# SubBus10.net
KiCad netlist of a schematic drawn in Altium Designer
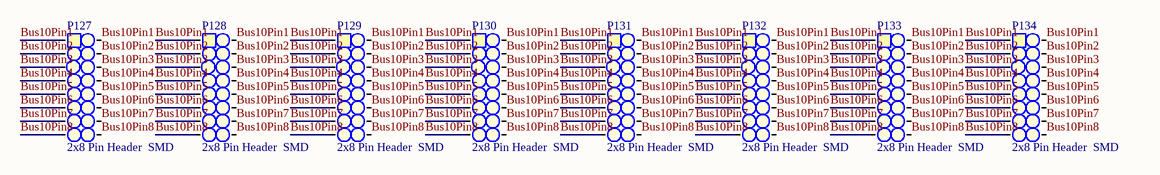
[diagram p0: SubBus10.SchDoc]

(export (version "E")
  (design (tool "Eeschema 10.0.6"))
  (components
    (comp (ref "P127")
      (value "2x8 Pin Header  SMD")
      (footprint "2X8_SMD_PH_2.54")
      (description "2.54mm, SMD")
      (libsource (lib "jclib") (part "2x8 Pin Header  SMD"))
    )
    (comp (ref "P128")
      (value "2x8 Pin Header  SMD")
      (footprint "2X8_SMD_PH_2.54")
      (description "2.54mm, SMD")
      (libsource (lib "jclib") (part "2x8 Pin Header  SMD"))
    )
    (comp (ref "P129")
      (value "2x8 Pin Header  SMD")
      (footprint "2X8_SMD_PH_2.54")
      (description "2.54mm, SMD")
      (libsource (lib "jclib") (part "2x8 Pin Header  SMD"))
    )
    (comp (ref "P130")
      (value "2x8 Pin Header  SMD")
      (footprint "2X8_SMD_PH_2.54")
      (description "2.54mm, SMD")
      (libsource (lib "jclib") (part "2x8 Pin Header  SMD"))
    )
    (comp (ref "P131")
      (value "2x8 Pin Header  SMD")
      (footprint "2X8_SMD_PH_2.54")
      (description "2.54mm, SMD")
      (libsource (lib "jclib") (part "2x8 Pin Header  SMD"))
    )
    (comp (ref "P132")
      (value "2x8 Pin Header  SMD")
      (footprint "2X8_SMD_PH_2.54")
      (description "2.54mm, SMD")
      (libsource (lib "jclib") (part "2x8 Pin Header  SMD"))
    )
    (comp (ref "P133")
      (value "2x8 Pin Header  SMD")
      (footprint "2X8_SMD_PH_2.54")
      (description "2.54mm, SMD")
      (libsource (lib "jclib") (part "2x8 Pin Header  SMD"))
    )
    (comp (ref "P134")
      (value "2x8 Pin Header  SMD")
      (footprint "2X8_SMD_PH_2.54")
      (description "2.54mm, SMD")
      (libsource (lib "jclib") (part "2x8 Pin Header  SMD"))
    )
  )
  (nets
    (net (code "1") (name "/Bus10Pin1") (class "Default")
      (node (ref "P127") (pin "1") (pinfunction "1_1") (pintype "passive"))
      (node (ref "P127") (pin "16") (pinfunction "16_16") (pintype "passive"))
      (node (ref "P128") (pin "1") (pinfunction "1_1") (pintype "passive"))
      (node (ref "P128") (pin "16") (pinfunction "16_16") (pintype "passive"))
      (node (ref "P129") (pin "1") (pinfunction "1_1") (pintype "passive"))
      (node (ref "P129") (pin "16") (pinfunction "16_16") (pintype "passive"))
      (node (ref "P130") (pin "1") (pinfunction "1_1") (pintype "passive"))
      (node (ref "P130") (pin "16") (pinfunction "16_16") (pintype "passive"))
      (node (ref "P131") (pin "1") (pinfunction "1_1") (pintype "passive"))
      (node (ref "P131") (pin "16") (pinfunction "16_16") (pintype "passive"))
      (node (ref "P132") (pin "1") (pinfunction "1_1") (pintype "passive"))
      (node (ref "P132") (pin "16") (pinfunction "16_16") (pintype "passive"))
      (node (ref "P133") (pin "1") (pinfunction "1_1") (pintype "passive"))
      (node (ref "P133") (pin "16") (pinfunction "16_16") (pintype "passive"))
      (node (ref "P134") (pin "1") (pinfunction "1_1") (pintype "passive"))
      (node (ref "P134") (pin "16") (pinfunction "16_16") (pintype "passive"))
    )
    (net (code "2") (name "/Bus10Pin2") (class "Default")
      (node (ref "P127") (pin "15") (pinfunction "15_15") (pintype "passive"))
      (node (ref "P127") (pin "2") (pinfunction "2_2") (pintype "passive"))
      (node (ref "P128") (pin "15") (pinfunction "15_15") (pintype "passive"))
      (node (ref "P128") (pin "2") (pinfunction "2_2") (pintype "passive"))
      (node (ref "P129") (pin "15") (pinfunction "15_15") (pintype "passive"))
      (node (ref "P129") (pin "2") (pinfunction "2_2") (pintype "passive"))
      (node (ref "P130") (pin "15") (pinfunction "15_15") (pintype "passive"))
      (node (ref "P130") (pin "2") (pinfunction "2_2") (pintype "passive"))
      (node (ref "P131") (pin "15") (pinfunction "15_15") (pintype "passive"))
      (node (ref "P131") (pin "2") (pinfunction "2_2") (pintype "passive"))
      (node (ref "P132") (pin "15") (pinfunction "15_15") (pintype "passive"))
      (node (ref "P132") (pin "2") (pinfunction "2_2") (pintype "passive"))
      (node (ref "P133") (pin "15") (pinfunction "15_15") (pintype "passive"))
      (node (ref "P133") (pin "2") (pinfunction "2_2") (pintype "passive"))
      (node (ref "P134") (pin "15") (pinfunction "15_15") (pintype "passive"))
      (node (ref "P134") (pin "2") (pinfunction "2_2") (pintype "passive"))
    )
    (net (code "3") (name "/Bus10Pin3") (class "Default")
      (node (ref "P127") (pin "14") (pinfunction "14_14") (pintype "passive"))
      (node (ref "P127") (pin "3") (pinfunction "3_3") (pintype "passive"))
      (node (ref "P128") (pin "14") (pinfunction "14_14") (pintype "passive"))
      (node (ref "P128") (pin "3") (pinfunction "3_3") (pintype "passive"))
      (node (ref "P129") (pin "14") (pinfunction "14_14") (pintype "passive"))
      (node (ref "P129") (pin "3") (pinfunction "3_3") (pintype "passive"))
      (node (ref "P130") (pin "14") (pinfunction "14_14") (pintype "passive"))
      (node (ref "P130") (pin "3") (pinfunction "3_3") (pintype "passive"))
      (node (ref "P131") (pin "14") (pinfunction "14_14") (pintype "passive"))
      (node (ref "P131") (pin "3") (pinfunction "3_3") (pintype "passive"))
      (node (ref "P132") (pin "14") (pinfunction "14_14") (pintype "passive"))
      (node (ref "P132") (pin "3") (pinfunction "3_3") (pintype "passive"))
      (node (ref "P133") (pin "14") (pinfunction "14_14") (pintype "passive"))
      (node (ref "P133") (pin "3") (pinfunction "3_3") (pintype "passive"))
      (node (ref "P134") (pin "14") (pinfunction "14_14") (pintype "passive"))
      (node (ref "P134") (pin "3") (pinfunction "3_3") (pintype "passive"))
    )
    (net (code "4") (name "/Bus10Pin4") (class "Default")
      (node (ref "P127") (pin "13") (pinfunction "13_13") (pintype "passive"))
      (node (ref "P127") (pin "4") (pinfunction "4_4") (pintype "passive"))
      (node (ref "P128") (pin "13") (pinfunction "13_13") (pintype "passive"))
      (node (ref "P128") (pin "4") (pinfunction "4_4") (pintype "passive"))
      (node (ref "P129") (pin "13") (pinfunction "13_13") (pintype "passive"))
      (node (ref "P129") (pin "4") (pinfunction "4_4") (pintype "passive"))
      (node (ref "P130") (pin "13") (pinfunction "13_13") (pintype "passive"))
      (node (ref "P130") (pin "4") (pinfunction "4_4") (pintype "passive"))
      (node (ref "P131") (pin "13") (pinfunction "13_13") (pintype "passive"))
      (node (ref "P131") (pin "4") (pinfunction "4_4") (pintype "passive"))
      (node (ref "P132") (pin "13") (pinfunction "13_13") (pintype "passive"))
      (node (ref "P132") (pin "4") (pinfunction "4_4") (pintype "passive"))
      (node (ref "P133") (pin "13") (pinfunction "13_13") (pintype "passive"))
      (node (ref "P133") (pin "4") (pinfunction "4_4") (pintype "passive"))
      (node (ref "P134") (pin "13") (pinfunction "13_13") (pintype "passive"))
      (node (ref "P134") (pin "4") (pinfunction "4_4") (pintype "passive"))
    )
    (net (code "5") (name "/Bus10Pin5") (class "Default")
      (node (ref "P127") (pin "12") (pinfunction "12_12") (pintype "passive"))
      (node (ref "P127") (pin "5") (pinfunction "5_5") (pintype "passive"))
      (node (ref "P128") (pin "12") (pinfunction "12_12") (pintype "passive"))
      (node (ref "P128") (pin "5") (pinfunction "5_5") (pintype "passive"))
      (node (ref "P129") (pin "12") (pinfunction "12_12") (pintype "passive"))
      (node (ref "P129") (pin "5") (pinfunction "5_5") (pintype "passive"))
      (node (ref "P130") (pin "12") (pinfunction "12_12") (pintype "passive"))
      (node (ref "P130") (pin "5") (pinfunction "5_5") (pintype "passive"))
      (node (ref "P131") (pin "12") (pinfunction "12_12") (pintype "passive"))
      (node (ref "P131") (pin "5") (pinfunction "5_5") (pintype "passive"))
      (node (ref "P132") (pin "12") (pinfunction "12_12") (pintype "passive"))
      (node (ref "P132") (pin "5") (pinfunction "5_5") (pintype "passive"))
      (node (ref "P133") (pin "12") (pinfunction "12_12") (pintype "passive"))
      (node (ref "P133") (pin "5") (pinfunction "5_5") (pintype "passive"))
      (node (ref "P134") (pin "12") (pinfunction "12_12") (pintype "passive"))
      (node (ref "P134") (pin "5") (pinfunction "5_5") (pintype "passive"))
    )
    (net (code "6") (name "/Bus10Pin6") (class "Default")
      (node (ref "P127") (pin "11") (pinfunction "11_11") (pintype "passive"))
      (node (ref "P127") (pin "6") (pinfunction "6_6") (pintype "passive"))
      (node (ref "P128") (pin "11") (pinfunction "11_11") (pintype "passive"))
      (node (ref "P128") (pin "6") (pinfunction "6_6") (pintype "passive"))
      (node (ref "P129") (pin "11") (pinfunction "11_11") (pintype "passive"))
      (node (ref "P129") (pin "6") (pinfunction "6_6") (pintype "passive"))
      (node (ref "P130") (pin "11") (pinfunction "11_11") (pintype "passive"))
      (node (ref "P130") (pin "6") (pinfunction "6_6") (pintype "passive"))
      (node (ref "P131") (pin "11") (pinfunction "11_11") (pintype "passive"))
      (node (ref "P131") (pin "6") (pinfunction "6_6") (pintype "passive"))
      (node (ref "P132") (pin "11") (pinfunction "11_11") (pintype "passive"))
      (node (ref "P132") (pin "6") (pinfunction "6_6") (pintype "passive"))
      (node (ref "P133") (pin "11") (pinfunction "11_11") (pintype "passive"))
      (node (ref "P133") (pin "6") (pinfunction "6_6") (pintype "passive"))
      (node (ref "P134") (pin "11") (pinfunction "11_11") (pintype "passive"))
      (node (ref "P134") (pin "6") (pinfunction "6_6") (pintype "passive"))
    )
    (net (code "7") (name "/Bus10Pin7") (class "Default")
      (node (ref "P127") (pin "10") (pinfunction "10_10") (pintype "passive"))
      (node (ref "P127") (pin "7") (pinfunction "7_7") (pintype "passive"))
      (node (ref "P128") (pin "10") (pinfunction "10_10") (pintype "passive"))
      (node (ref "P128") (pin "7") (pinfunction "7_7") (pintype "passive"))
      (node (ref "P129") (pin "10") (pinfunction "10_10") (pintype "passive"))
      (node (ref "P129") (pin "7") (pinfunction "7_7") (pintype "passive"))
      (node (ref "P130") (pin "10") (pinfunction "10_10") (pintype "passive"))
      (node (ref "P130") (pin "7") (pinfunction "7_7") (pintype "passive"))
      (node (ref "P131") (pin "10") (pinfunction "10_10") (pintype "passive"))
      (node (ref "P131") (pin "7") (pinfunction "7_7") (pintype "passive"))
      (node (ref "P132") (pin "10") (pinfunction "10_10") (pintype "passive"))
      (node (ref "P132") (pin "7") (pinfunction "7_7") (pintype "passive"))
      (node (ref "P133") (pin "10") (pinfunction "10_10") (pintype "passive"))
      (node (ref "P133") (pin "7") (pinfunction "7_7") (pintype "passive"))
      (node (ref "P134") (pin "10") (pinfunction "10_10") (pintype "passive"))
      (node (ref "P134") (pin "7") (pinfunction "7_7") (pintype "passive"))
    )
    (net (code "8") (name "/Bus10Pin8") (class "Default")
      (node (ref "P127") (pin "8") (pinfunction "8_8") (pintype "passive"))
      (node (ref "P127") (pin "9") (pinfunction "9_9") (pintype "passive"))
      (node (ref "P128") (pin "8") (pinfunction "8_8") (pintype "passive"))
      (node (ref "P128") (pin "9") (pinfunction "9_9") (pintype "passive"))
      (node (ref "P129") (pin "8") (pinfunction "8_8") (pintype "passive"))
      (node (ref "P129") (pin "9") (pinfunction "9_9") (pintype "passive"))
      (node (ref "P130") (pin "8") (pinfunction "8_8") (pintype "passive"))
      (node (ref "P130") (pin "9") (pinfunction "9_9") (pintype "passive"))
      (node (ref "P131") (pin "8") (pinfunction "8_8") (pintype "passive"))
      (node (ref "P131") (pin "9") (pinfunction "9_9") (pintype "passive"))
      (node (ref "P132") (pin "8") (pinfunction "8_8") (pintype "passive"))
      (node (ref "P132") (pin "9") (pinfunction "9_9") (pintype "passive"))
      (node (ref "P133") (pin "8") (pinfunction "8_8") (pintype "passive"))
      (node (ref "P133") (pin "9") (pinfunction "9_9") (pintype "passive"))
      (node (ref "P134") (pin "8") (pinfunction "8_8") (pintype "passive"))
      (node (ref "P134") (pin "9") (pinfunction "9_9") (pintype "passive"))
    )
  )
)
